# USB-Knob.net
KiCad netlist of a schematic drawn in EAGLE
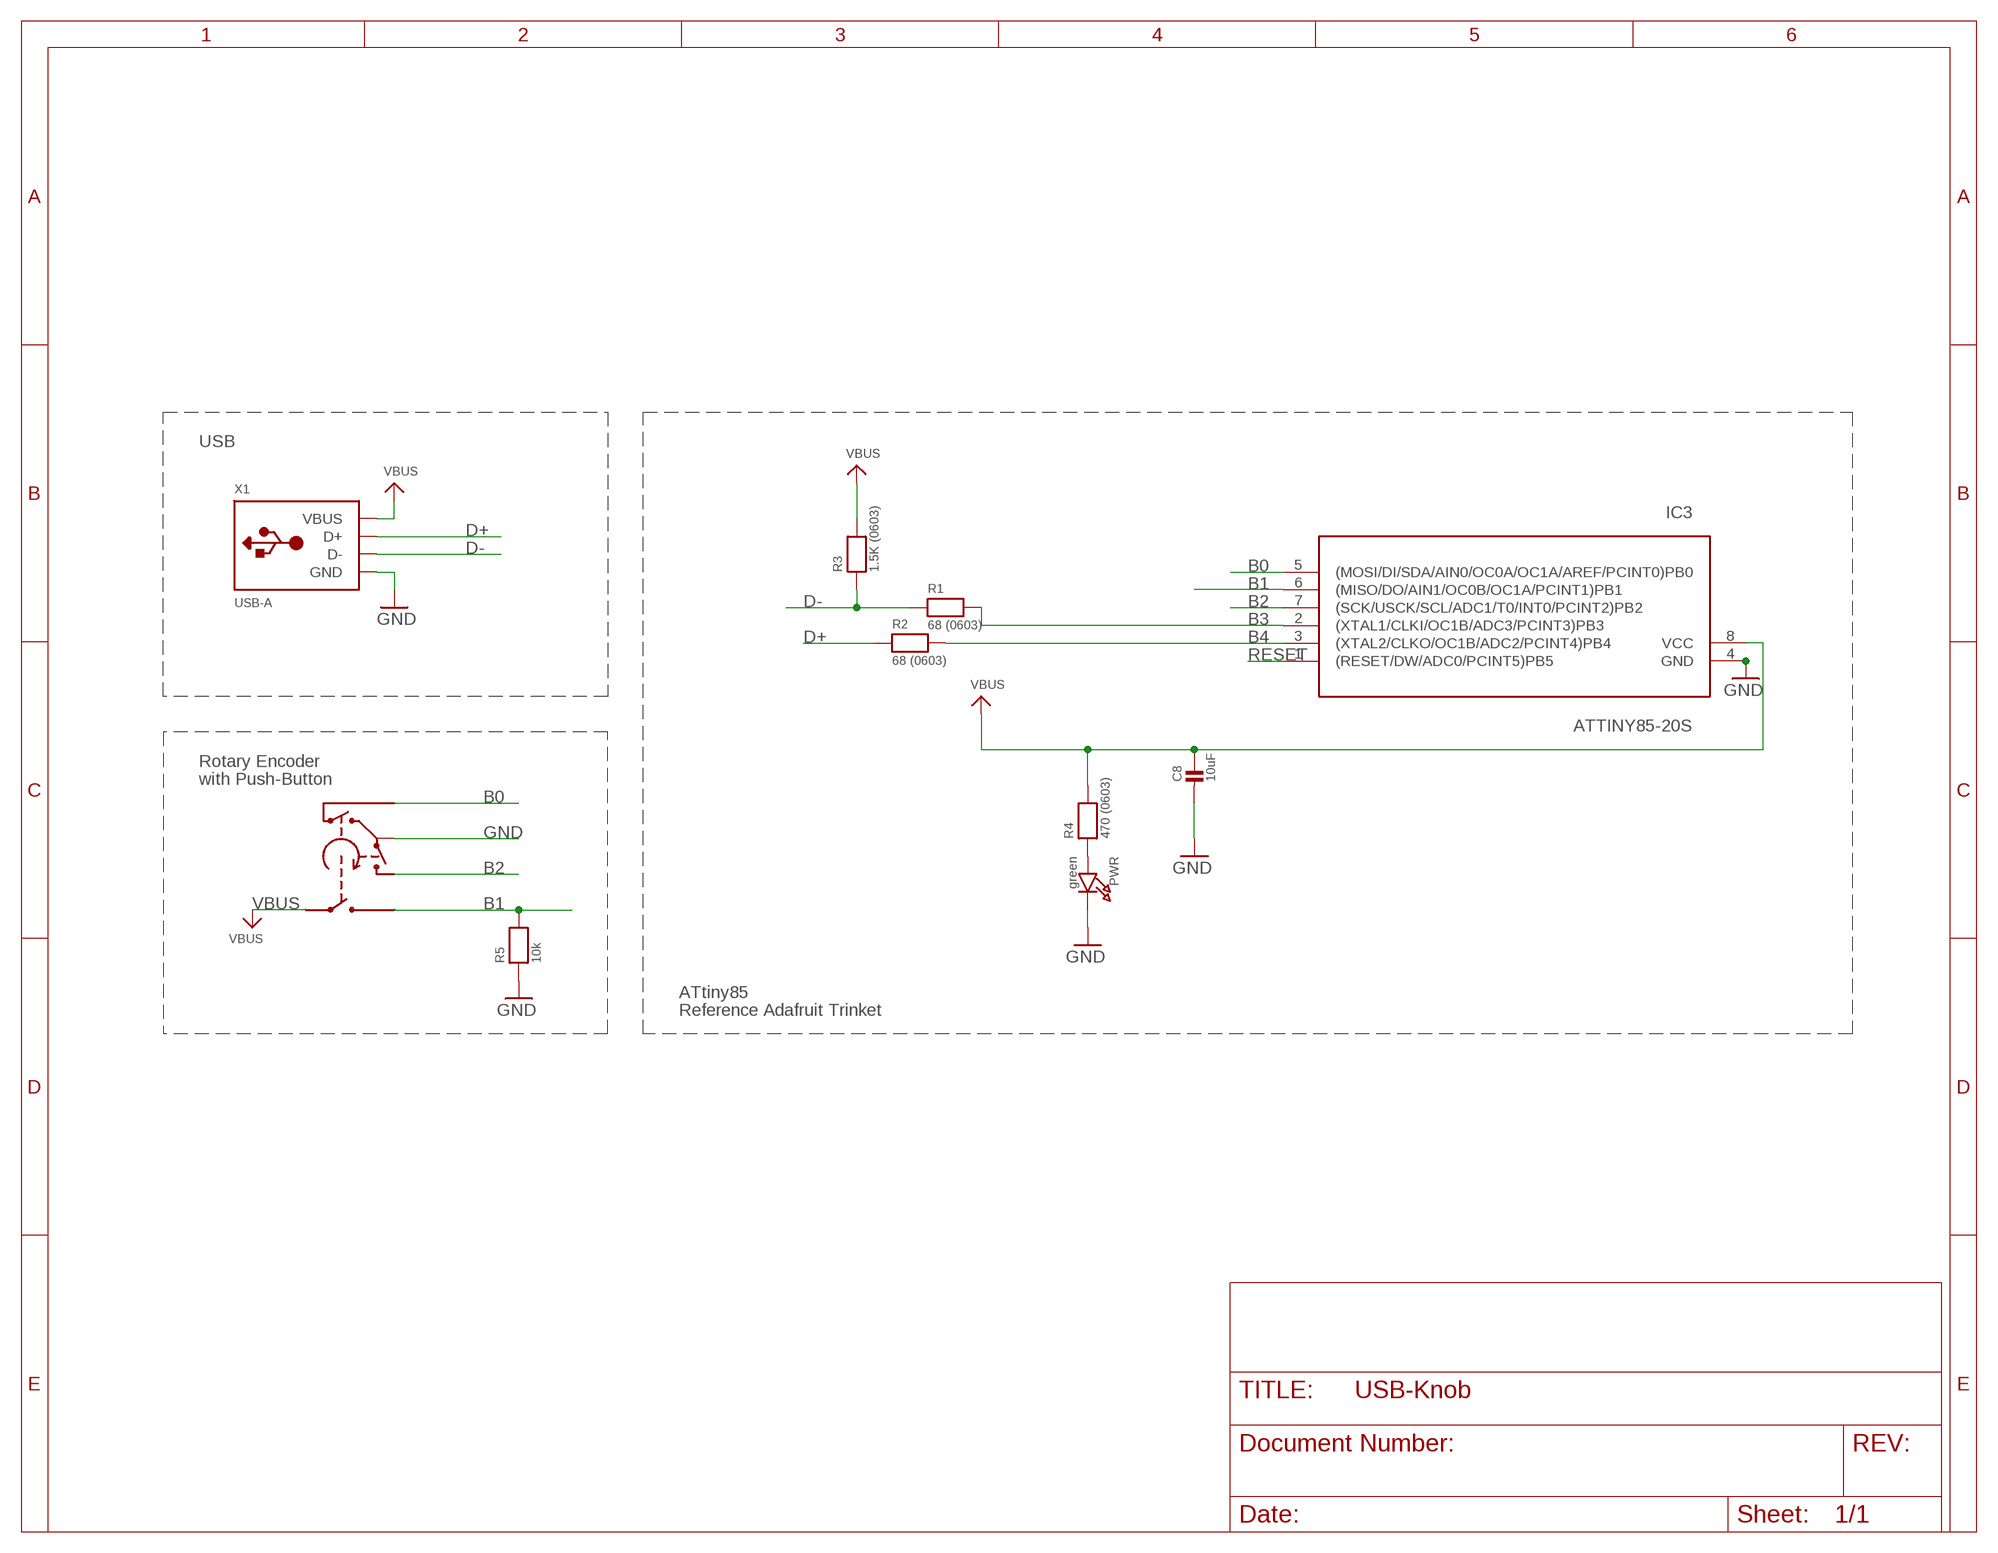
[diagram p0: schematic, sheet 1]

(export (version "E")
  (design (tool "Eeschema 10.0.6"))
  (components
    (comp (ref "C8")
      (value "10uF")
      (footprint "eagle-import:0805-NO")
      (libsource (lib "eagle-import") (part "CAP_CERAMIC0805-NOOUTLINE"))
    )
    (comp (ref "IC3")
      (value "ATTINY85-20S")
      (footprint "eagle-import:SOIC8")
      (libsource (lib "eagle-import") (part "ATTINY85SV-10"))
    )
    (comp (ref "PWR")
      (value "green")
      (footprint "eagle-import:CHIPLED_0805_NOOUTLINE")
      (libsource (lib "eagle-import") (part "LED0805_NOOUTLINE"))
    )
    (comp (ref "R1")
      (value "68 (0603)")
      (footprint "eagle-import:0603-NO")
      (libsource (lib "eagle-import") (part "RESISTOR_0603_NOOUT"))
    )
    (comp (ref "R2")
      (value "68 (0603)")
      (footprint "eagle-import:0603-NO")
      (libsource (lib "eagle-import") (part "RESISTOR_0603_NOOUT"))
    )
    (comp (ref "R3")
      (value "1.5K (0603)")
      (footprint "eagle-import:0603-NO")
      (libsource (lib "eagle-import") (part "RESISTOR_0603_NOOUT"))
    )
    (comp (ref "R4")
      (value "470 (0603)")
      (footprint "eagle-import:0603-NO")
      (libsource (lib "eagle-import") (part "RESISTOR_0603_NOOUT"))
    )
    (comp (ref "R5")
      (value "10k")
      (footprint "eagle-import:0603-NO")
      (libsource (lib "eagle-import") (part "RESISTOR_0603_NOOUT"))
    )
    (comp (ref "U$2")
      (value "ALPHA-ROT-ENCODER")
      (footprint "eagle-import:TW-700198")
      (libsource (lib "eagle-import") (part "ALPHA-ROT-ENCODER"))
    )
    (comp (ref "X1")
      (value "USB-A")
      (footprint "eagle-import:MOLEX_480371000")
      (libsource (lib "eagle-import") (part "USB-A"))
    )
  )
  (nets
    (net (code "1") (name "/B0") (class "Default")
      (node (ref "IC3") (pin "5") (pinfunction "(MOSI/DI/SDA/AIN0/OC0A/OC1A/AREF/PCINT0)PB0_5") (pintype "bidirectional"))
      (node (ref "U$2") (pin "P3") (pinfunction "A_P3") (pintype "passive"))
    )
    (net (code "2") (name "/B1") (class "Default")
      (node (ref "IC3") (pin "6") (pinfunction "(MISO/DO/AIN1/OC0B/OC1A/PCINT1)PB1_6") (pintype "bidirectional"))
      (node (ref "R5") (pin "2") (pinfunction "2_2") (pintype "passive"))
      (node (ref "U$2") (pin "P5") (pinfunction "S2_P5") (pintype "passive"))
    )
    (net (code "3") (name "/B2") (class "Default")
      (node (ref "IC3") (pin "7") (pinfunction "(SCK/USCK/SCL/ADC1/T0/INT0/PCINT2)PB2_7") (pintype "bidirectional"))
      (node (ref "U$2") (pin "P1") (pinfunction "B_P1") (pintype "passive"))
    )
    (net (code "4") (name "/B3") (class "Default")
      (node (ref "IC3") (pin "2") (pinfunction "(XTAL1/CLKI/OC1B/ADC3/PCINT3)PB3_2") (pintype "bidirectional"))
      (node (ref "R1") (pin "2") (pinfunction "2_2") (pintype "passive"))
    )
    (net (code "5") (name "/B4") (class "Default")
      (node (ref "IC3") (pin "3") (pinfunction "(XTAL2/CLKO/OC1B/ADC2/PCINT4)PB4_3") (pintype "bidirectional"))
      (node (ref "R2") (pin "2") (pinfunction "2_2") (pintype "passive"))
    )
    (net (code "6") (name "/D+") (class "Default")
      (node (ref "R2") (pin "1") (pinfunction "1_1") (pintype "passive"))
      (node (ref "X1") (pin "3") (pinfunction "D+_3") (pintype "bidirectional"))
    )
    (net (code "7") (name "/D-") (class "Default")
      (node (ref "R1") (pin "1") (pinfunction "1_1") (pintype "passive"))
      (node (ref "R3") (pin "1") (pinfunction "1_1") (pintype "passive"))
      (node (ref "X1") (pin "2") (pinfunction "D-_2") (pintype "bidirectional"))
    )
    (net (code "8") (name "/RESET") (class "Default")
      (node (ref "IC3") (pin "1") (pinfunction "(RESET/DW/ADC0/PCINT5)PB5_1") (pintype "bidirectional"))
    )
    (net (code "9") (name "GND") (class "Default")
      (node (ref "C8") (pin "2") (pinfunction "2_2") (pintype "passive"))
      (node (ref "IC3") (pin "4") (pinfunction "GND_4") (pintype "bidirectional"))
      (node (ref "PWR") (pin "C") (pinfunction "C_C") (pintype "passive"))
      (node (ref "R5") (pin "1") (pinfunction "1_1") (pintype "passive"))
      (node (ref "U$2") (pin "P2") (pinfunction "COM_P2") (pintype "passive"))
      (node (ref "X1") (pin "4") (pinfunction "GND_4") (pintype "power_in"))
    )
    (net (code "10") (name "Net-(PWR-PadA)") (class "Default")
      (node (ref "PWR") (pin "A") (pinfunction "A_A") (pintype "passive"))
      (node (ref "R4") (pin "1") (pinfunction "1_1") (pintype "passive"))
    )
    (net (code "11") (name "VBUS") (class "Default")
      (node (ref "C8") (pin "1") (pinfunction "1_1") (pintype "passive"))
      (node (ref "IC3") (pin "8") (pinfunction "VCC_8") (pintype "bidirectional"))
      (node (ref "R3") (pin "2") (pinfunction "2_2") (pintype "passive"))
      (node (ref "R4") (pin "2") (pinfunction "2_2") (pintype "passive"))
      (node (ref "U$2") (pin "P4") (pinfunction "S1_P4") (pintype "passive"))
      (node (ref "X1") (pin "1") (pinfunction "VBUS_1") (pintype "power_in"))
    )
  )
)
